# XLR.net
KiCad netlist of a schematic drawn in EAGLE
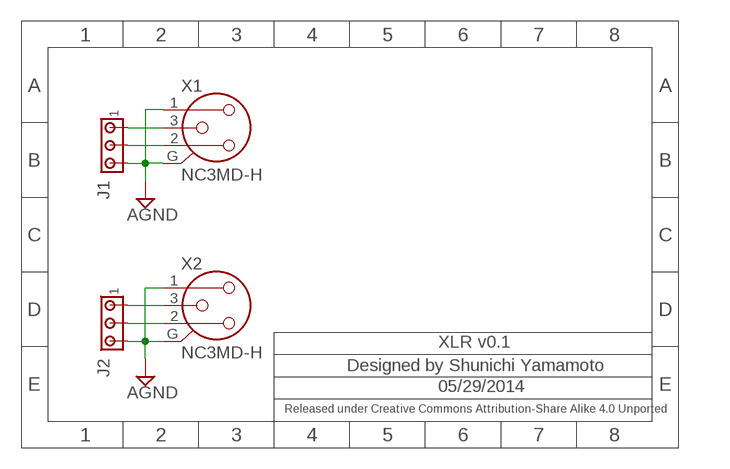
[diagram p0: schematic, sheet 1]

(export (version "E")
  (design (tool "Eeschema 10.0.6"))
  (components
    (comp (ref "J1")
      (value "MTA03-100")
      (footprint "eagle-import:10X03MTA")
      (libsource (lib "eagle-import") (part "MTA03-100"))
    )
    (comp (ref "J2")
      (value "MTA03-100")
      (footprint "eagle-import:10X03MTA")
      (libsource (lib "eagle-import") (part "MTA03-100"))
    )
    (comp (ref "X1")
      (value "NC3MD-H")
      (footprint "eagle-import:NC3MD-H")
      (fields (field (name "MF") "NEUTRIK"))
      (libsource (lib "eagle-import") (part "NC3MD-H"))
    )
    (comp (ref "X2")
      (value "NC3MD-H")
      (footprint "eagle-import:NC3MD-H")
      (fields (field (name "MF") "NEUTRIK"))
      (libsource (lib "eagle-import") (part "NC3MD-H"))
    )
  )
  (nets
    (net (code "1") (name "AGND") (class "Default")
      (node (ref "J1") (pin "3") (pinfunction "3_3") (pintype "passive"))
      (node (ref "J2") (pin "3") (pinfunction "3_3") (pintype "passive"))
      (node (ref "X1") (pin "1") (pinfunction "1_1") (pintype "passive"))
      (node (ref "X1") (pin "G") (pinfunction "G_G") (pintype "passive"))
      (node (ref "X2") (pin "1") (pinfunction "1_1") (pintype "passive"))
      (node (ref "X2") (pin "G") (pinfunction "G_G") (pintype "passive"))
    )
    (net (code "2") (name "Net-(J1-Pad1)") (class "Default")
      (node (ref "J1") (pin "1") (pinfunction "1_1") (pintype "passive"))
      (node (ref "X1") (pin "3") (pinfunction "3_3") (pintype "passive"))
    )
    (net (code "3") (name "Net-(J1-Pad2)") (class "Default")
      (node (ref "J1") (pin "2") (pinfunction "2_2") (pintype "passive"))
      (node (ref "X1") (pin "2") (pinfunction "2_2") (pintype "passive"))
    )
    (net (code "4") (name "Net-(J2-Pad1)") (class "Default")
      (node (ref "J2") (pin "1") (pinfunction "1_1") (pintype "passive"))
      (node (ref "X2") (pin "3") (pinfunction "3_3") (pintype "passive"))
    )
    (net (code "5") (name "Net-(J2-Pad2)") (class "Default")
      (node (ref "J2") (pin "2") (pinfunction "2_2") (pintype "passive"))
      (node (ref "X2") (pin "2") (pinfunction "2_2") (pintype "passive"))
    )
  )
)
